# logger.net
KiCad netlist of a schematic drawn in EAGLE
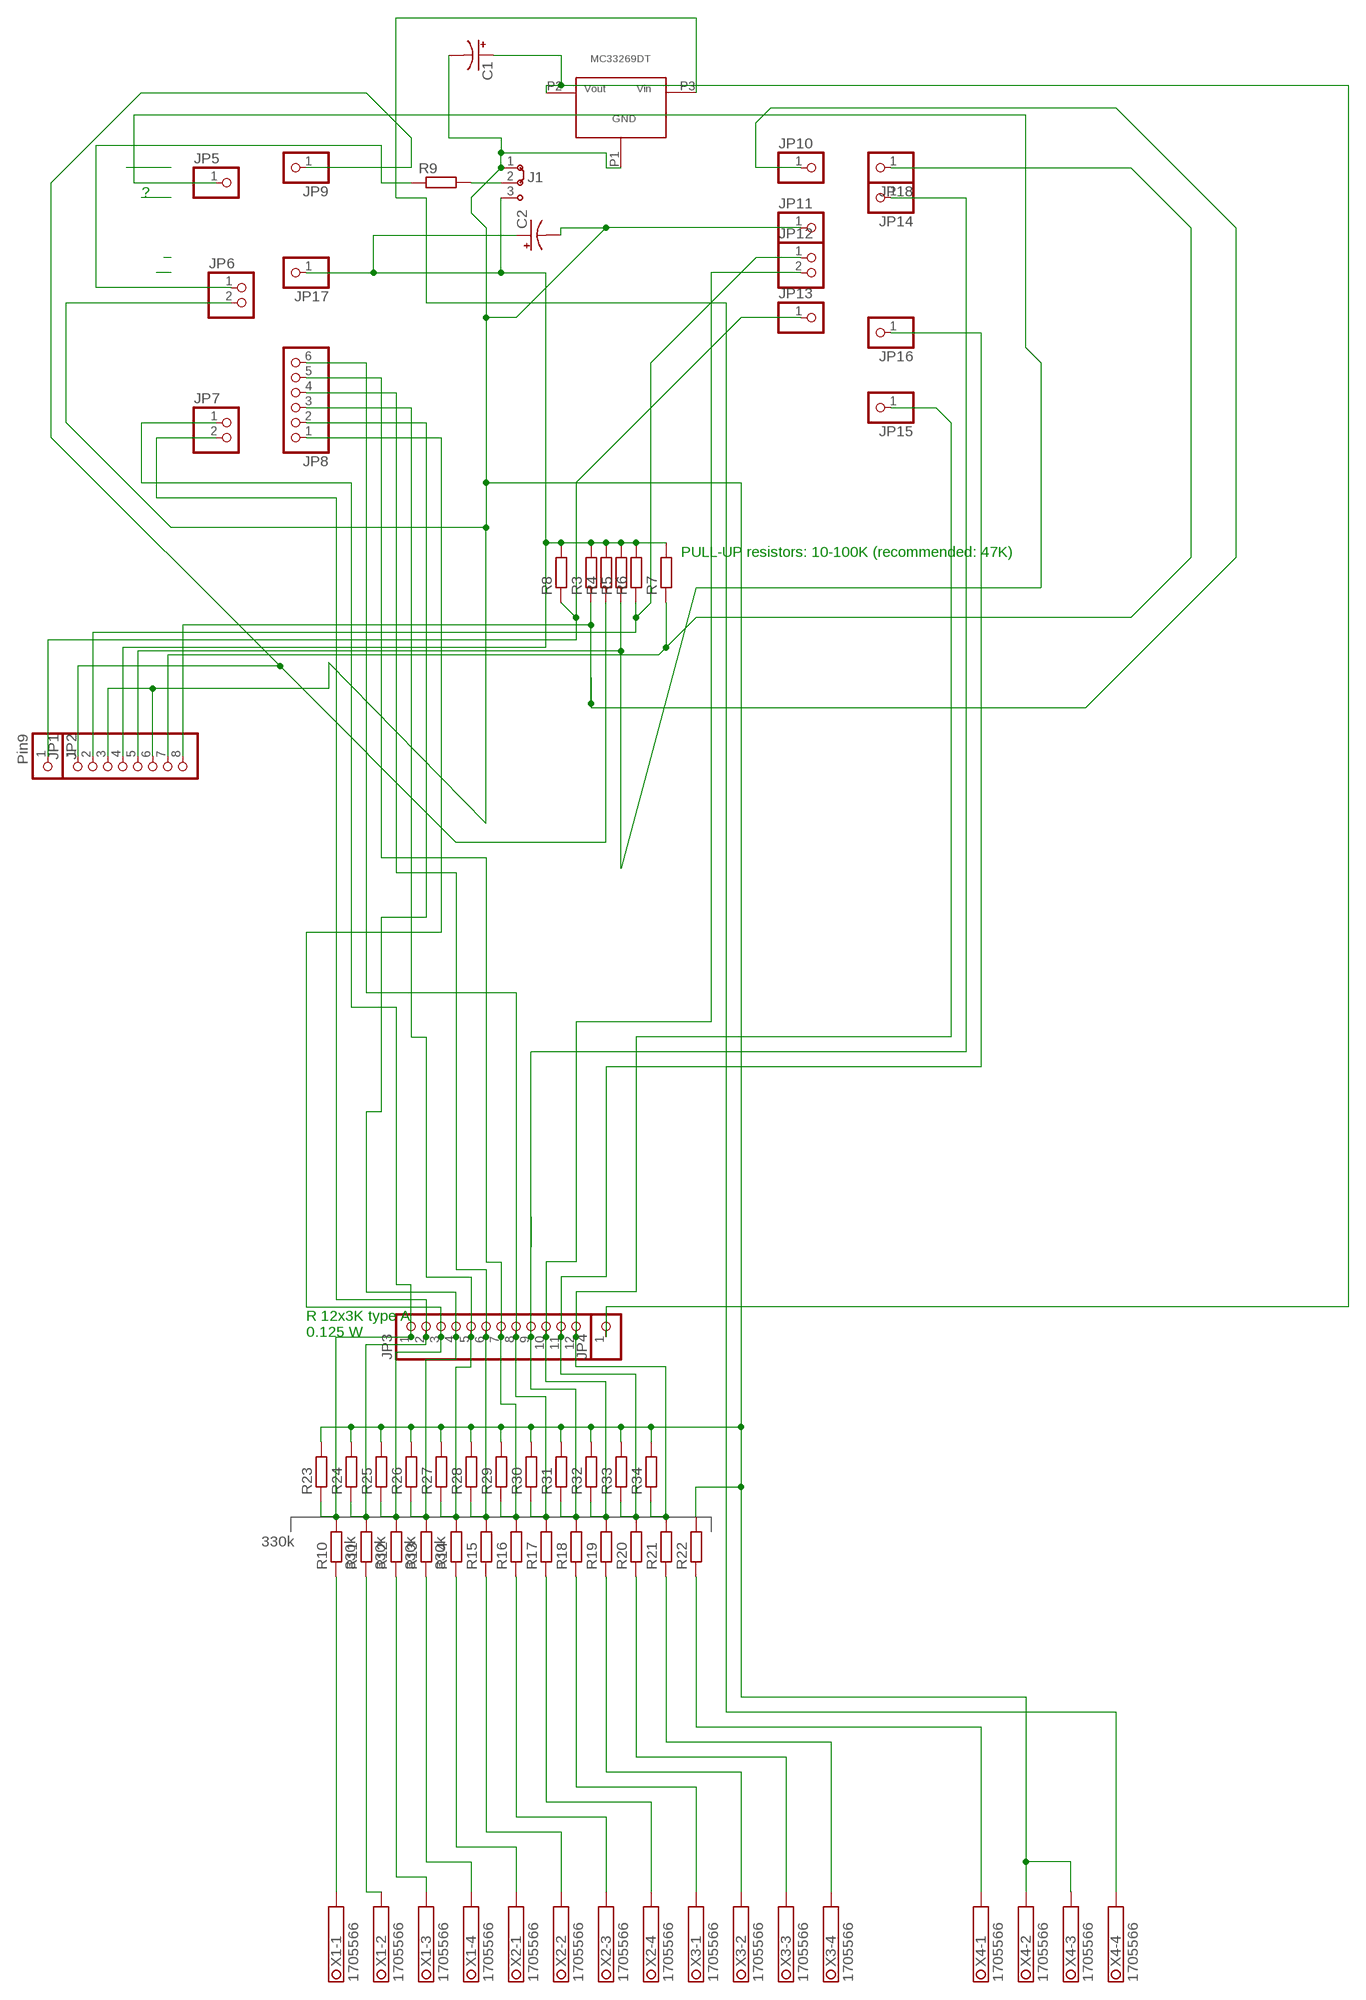
[diagram p0: schematic, sheet 1]

(export (version "E")
  (design (tool "Eeschema 10.0.6"))
  (components
    (comp (ref "C1")
      (value "CPOL-USE5-10.5")
      (footprint "eagle-import:E5-10,5")
      (libsource (lib "eagle-import") (part "CPOL-USE5-10.5"))
    )
    (comp (ref "C2")
      (value "CPOL-USE5-10.5")
      (footprint "eagle-import:E5-10,5")
      (libsource (lib "eagle-import") (part "CPOL-USE5-10.5"))
    )
    (comp (ref "J1")
      (value "J2X2MM")
      (footprint "eagle-import:04C")
      (libsource (lib "eagle-import") (part "J2X2MM"))
    )
    (comp (ref "JP1")
      (value "PINHD-1X8")
      (footprint "eagle-import:1X08")
      (libsource (lib "eagle-import") (part "PINHD-1X8"))
    )
    (comp (ref "JP2")
      (value "Pin9")
      (footprint "eagle-import:1X01")
      (libsource (lib "eagle-import") (part "PINHD-1X1"))
    )
    (comp (ref "JP3")
      (value "PINHD-1X12")
      (footprint "eagle-import:1X12")
      (libsource (lib "eagle-import") (part "PINHD-1X12"))
    )
    (comp (ref "JP4")
      (value "PINHD-1X1")
      (footprint "eagle-import:1X01")
      (libsource (lib "eagle-import") (part "PINHD-1X1"))
    )
    (comp (ref "JP5")
      (value "PINHD-1X1")
      (footprint "eagle-import:1X01")
      (libsource (lib "eagle-import") (part "PINHD-1X1"))
    )
    (comp (ref "JP6")
      (value "PINHD-1X2")
      (footprint "eagle-import:1X02")
      (libsource (lib "eagle-import") (part "PINHD-1X2"))
    )
    (comp (ref "JP7")
      (value "PINHD-1X2")
      (footprint "eagle-import:1X02")
      (libsource (lib "eagle-import") (part "PINHD-1X2"))
    )
    (comp (ref "JP8")
      (value "PINHD-1X6")
      (footprint "eagle-import:1X06")
      (libsource (lib "eagle-import") (part "PINHD-1X6"))
    )
    (comp (ref "JP9")
      (value "PINHD-1X1")
      (footprint "eagle-import:1X01")
      (libsource (lib "eagle-import") (part "PINHD-1X1"))
    )
    (comp (ref "JP10")
      (value "PINHD-1X1")
      (footprint "eagle-import:1X01")
      (libsource (lib "eagle-import") (part "PINHD-1X1"))
    )
    (comp (ref "JP11")
      (value "PINHD-1X1")
      (footprint "eagle-import:1X01")
      (libsource (lib "eagle-import") (part "PINHD-1X1"))
    )
    (comp (ref "JP12")
      (value "PINHD-1X2")
      (footprint "eagle-import:1X02")
      (libsource (lib "eagle-import") (part "PINHD-1X2"))
    )
    (comp (ref "JP13")
      (value "PINHD-1X1")
      (footprint "eagle-import:1X01")
      (libsource (lib "eagle-import") (part "PINHD-1X1"))
    )
    (comp (ref "JP14")
      (value "PINHD-1X1")
      (footprint "eagle-import:1X01")
      (libsource (lib "eagle-import") (part "PINHD-1X1"))
    )
    (comp (ref "JP15")
      (value "PINHD-1X1")
      (footprint "eagle-import:1X01")
      (libsource (lib "eagle-import") (part "PINHD-1X1"))
    )
    (comp (ref "JP16")
      (value "PINHD-1X1")
      (footprint "eagle-import:1X01")
      (libsource (lib "eagle-import") (part "PINHD-1X1"))
    )
    (comp (ref "JP17")
      (value "PINHD-1X1")
      (footprint "eagle-import:1X01")
      (libsource (lib "eagle-import") (part "PINHD-1X1"))
    )
    (comp (ref "JP18")
      (value "PINHD-1X1")
      (footprint "eagle-import:1X01")
      (libsource (lib "eagle-import") (part "PINHD-1X1"))
    )
    (comp (ref "R3")
      (value "R-EU_R1206")
      (footprint "eagle-import:R1206")
      (libsource (lib "eagle-import") (part "R-EU_R1206"))
    )
    (comp (ref "R4")
      (value "R-EU_R1206")
      (footprint "eagle-import:R1206")
      (libsource (lib "eagle-import") (part "R-EU_R1206"))
    )
    (comp (ref "R5")
      (value "R-EU_R1206")
      (footprint "eagle-import:R1206")
      (libsource (lib "eagle-import") (part "R-EU_R1206"))
    )
    (comp (ref "R6")
      (value "R-EU_R1206")
      (footprint "eagle-import:R1206")
      (libsource (lib "eagle-import") (part "R-EU_R1206"))
    )
    (comp (ref "R7")
      (value "R-EU_R1206")
      (footprint "eagle-import:R1206")
      (libsource (lib "eagle-import") (part "R-EU_R1206"))
    )
    (comp (ref "R8")
      (value "R-EU_R1206")
      (footprint "eagle-import:R1206")
      (libsource (lib "eagle-import") (part "R-EU_R1206"))
    )
    (comp (ref "R9")
      (value "R-EU_R1206")
      (footprint "eagle-import:R1206")
      (libsource (lib "eagle-import") (part "R-EU_R1206"))
    )
    (comp (ref "R10")
      (value "330k")
      (footprint "eagle-import:0207_15")
      (libsource (lib "eagle-import") (part "R-EU_0207/15"))
    )
    (comp (ref "R11")
      (value "330k")
      (footprint "eagle-import:0207_15")
      (libsource (lib "eagle-import") (part "R-EU_0207/15"))
    )
    (comp (ref "R12")
      (value "330k")
      (footprint "eagle-import:0207_15")
      (libsource (lib "eagle-import") (part "R-EU_0207/15"))
    )
    (comp (ref "R13")
      (value "330k")
      (footprint "eagle-import:0207_15")
      (libsource (lib "eagle-import") (part "R-EU_0207/15"))
    )
    (comp (ref "R14")
      (value "R-EU_0207/15")
      (footprint "eagle-import:0207_15")
      (libsource (lib "eagle-import") (part "R-EU_0207/15"))
    )
    (comp (ref "R15")
      (value "R-EU_0207/15")
      (footprint "eagle-import:0207_15")
      (libsource (lib "eagle-import") (part "R-EU_0207/15"))
    )
    (comp (ref "R16")
      (value "R-EU_0207/15")
      (footprint "eagle-import:0207_15")
      (libsource (lib "eagle-import") (part "R-EU_0207/15"))
    )
    (comp (ref "R17")
      (value "R-EU_0207/15")
      (footprint "eagle-import:0207_15")
      (libsource (lib "eagle-import") (part "R-EU_0207/15"))
    )
    (comp (ref "R18")
      (value "R-EU_0207/15")
      (footprint "eagle-import:0207_15")
      (libsource (lib "eagle-import") (part "R-EU_0207/15"))
    )
    (comp (ref "R19")
      (value "R-EU_0207/15")
      (footprint "eagle-import:0207_15")
      (libsource (lib "eagle-import") (part "R-EU_0207/15"))
    )
    (comp (ref "R20")
      (value "R-EU_0207/15")
      (footprint "eagle-import:0207_15")
      (libsource (lib "eagle-import") (part "R-EU_0207/15"))
    )
    (comp (ref "R21")
      (value "R-EU_0207/15")
      (footprint "eagle-import:0207_15")
      (libsource (lib "eagle-import") (part "R-EU_0207/15"))
    )
    (comp (ref "R22")
      (value "R-EU_0207/15")
      (footprint "eagle-import:0207_15")
      (libsource (lib "eagle-import") (part "R-EU_0207/15"))
    )
    (comp (ref "R23")
      (value "R-EU_R1206")
      (footprint "eagle-import:R1206")
      (libsource (lib "eagle-import") (part "R-EU_R1206"))
    )
    (comp (ref "R24")
      (value "R-EU_R1206")
      (footprint "eagle-import:R1206")
      (libsource (lib "eagle-import") (part "R-EU_R1206"))
    )
    (comp (ref "R25")
      (value "R-EU_R1206")
      (footprint "eagle-import:R1206")
      (libsource (lib "eagle-import") (part "R-EU_R1206"))
    )
    (comp (ref "R26")
      (value "R-EU_R1206")
      (footprint "eagle-import:R1206")
      (libsource (lib "eagle-import") (part "R-EU_R1206"))
    )
    (comp (ref "R27")
      (value "R-EU_R1206")
      (footprint "eagle-import:R1206")
      (libsource (lib "eagle-import") (part "R-EU_R1206"))
    )
    (comp (ref "R28")
      (value "R-EU_R1206")
      (footprint "eagle-import:R1206")
      (libsource (lib "eagle-import") (part "R-EU_R1206"))
    )
    (comp (ref "R29")
      (value "R-EU_R1206")
      (footprint "eagle-import:R1206")
      (libsource (lib "eagle-import") (part "R-EU_R1206"))
    )
    (comp (ref "R30")
      (value "R-EU_R1206")
      (footprint "eagle-import:R1206")
      (libsource (lib "eagle-import") (part "R-EU_R1206"))
    )
    (comp (ref "R31")
      (value "R-EU_R1206")
      (footprint "eagle-import:R1206")
      (libsource (lib "eagle-import") (part "R-EU_R1206"))
    )
    (comp (ref "R32")
      (value "R-EU_R1206")
      (footprint "eagle-import:R1206")
      (libsource (lib "eagle-import") (part "R-EU_R1206"))
    )
    (comp (ref "R33")
      (value "R-EU_R1206")
      (footprint "eagle-import:R1206")
      (libsource (lib "eagle-import") (part "R-EU_R1206"))
    )
    (comp (ref "R34")
      (value "R-EU_R1206")
      (footprint "eagle-import:R1206")
      (libsource (lib "eagle-import") (part "R-EU_R1206"))
    )
    (comp (ref "U$2")
      (value "MC33269DT")
      (footprint "eagle-import:MC33269DT")
      (libsource (lib "eagle-import") (part "MC33269DT"))
    )
    (comp (ref "X1")
      (value "1705566")
      (footprint "eagle-import:1705566")
      (libsource (lib "eagle-import") (part "1705566"))
    )
    (comp (ref "X2")
      (value "1705566")
      (footprint "eagle-import:1705566")
      (libsource (lib "eagle-import") (part "1705566"))
    )
    (comp (ref "X3")
      (value "1705566")
      (footprint "eagle-import:1705566")
      (libsource (lib "eagle-import") (part "1705566"))
    )
    (comp (ref "X4")
      (value "1705566")
      (footprint "eagle-import:1705566")
      (libsource (lib "eagle-import") (part "1705566"))
    )
  )
  (nets
    (net (code "1") (name "Net-(C2-Pad+)") (class "Default")
      (node (ref "C2") (pin "+") (pinfunction "+_+") (pintype "passive"))
      (node (ref "J1") (pin "3") (pinfunction "3_3") (pintype "passive"))
      (node (ref "JP1") (pin "4") (pinfunction "4_4") (pintype "passive"))
      (node (ref "JP17") (pin "1") (pinfunction "1_1") (pintype "passive"))
      (node (ref "R3") (pin "2") (pinfunction "2_2") (pintype "passive"))
      (node (ref "R4") (pin "2") (pinfunction "2_2") (pintype "passive"))
      (node (ref "R5") (pin "2") (pinfunction "2_2") (pintype "passive"))
      (node (ref "R6") (pin "2") (pinfunction "2_2") (pintype "passive"))
      (node (ref "R7") (pin "2") (pinfunction "2_2") (pintype "passive"))
      (node (ref "R8") (pin "2") (pinfunction "2_2") (pintype "passive"))
    )
    (net (code "2") (name "Net-(J1-Pad2)") (class "Default")
      (node (ref "J1") (pin "2") (pinfunction "2_2") (pintype "passive"))
      (node (ref "R9") (pin "2") (pinfunction "2_2") (pintype "passive"))
    )
    (net (code "3") (name "Net-(JP1-Pad1)") (class "Default")
      (node (ref "JP1") (pin "1") (pinfunction "1_1") (pintype "passive"))
      (node (ref "JP9") (pin "1") (pinfunction "1_1") (pintype "passive"))
      (node (ref "R4") (pin "1") (pinfunction "1_1") (pintype "passive"))
    )
    (net (code "4") (name "Net-(JP1-Pad2)") (class "Default")
      (node (ref "JP1") (pin "2") (pinfunction "2_2") (pintype "passive"))
      (node (ref "JP12") (pin "1") (pinfunction "1_1") (pintype "passive"))
      (node (ref "R6") (pin "1") (pinfunction "1_1") (pintype "passive"))
    )
    (net (code "5") (name "Net-(JP1-Pad5)") (class "Default")
      (node (ref "JP1") (pin "5") (pinfunction "5_5") (pintype "passive"))
      (node (ref "JP5") (pin "1") (pinfunction "1_1") (pintype "passive"))
      (node (ref "R5") (pin "1") (pinfunction "1_1") (pintype "passive"))
    )
    (net (code "6") (name "Net-(JP1-Pad7)") (class "Default")
      (node (ref "JP1") (pin "7") (pinfunction "7_7") (pintype "passive"))
      (node (ref "JP18") (pin "1") (pinfunction "1_1") (pintype "passive"))
      (node (ref "R7") (pin "1") (pinfunction "1_1") (pintype "passive"))
    )
    (net (code "7") (name "Net-(JP1-Pad8)") (class "Default")
      (node (ref "JP1") (pin "8") (pinfunction "8_8") (pintype "passive"))
      (node (ref "JP10") (pin "1") (pinfunction "1_1") (pintype "passive"))
      (node (ref "R3") (pin "1") (pinfunction "1_1") (pintype "passive"))
    )
    (net (code "8") (name "Net-(JP3-Pad1)") (class "Default")
      (node (ref "JP3") (pin "1") (pinfunction "1_1") (pintype "passive"))
      (node (ref "JP7") (pin "1") (pinfunction "1_1") (pintype "passive"))
      (node (ref "R10") (pin "2") (pinfunction "2_2") (pintype "passive"))
      (node (ref "R23") (pin "1") (pinfunction "1_1") (pintype "passive"))
    )
    (net (code "9") (name "Net-(JP3-Pad2)") (class "Default")
      (node (ref "JP3") (pin "2") (pinfunction "2_2") (pintype "passive"))
      (node (ref "JP7") (pin "2") (pinfunction "2_2") (pintype "passive"))
      (node (ref "R11") (pin "2") (pinfunction "2_2") (pintype "passive"))
      (node (ref "R24") (pin "1") (pinfunction "1_1") (pintype "passive"))
    )
    (net (code "10") (name "Net-(JP3-Pad3)") (class "Default")
      (node (ref "JP3") (pin "3") (pinfunction "3_3") (pintype "passive"))
      (node (ref "JP8") (pin "1") (pinfunction "1_1") (pintype "passive"))
      (node (ref "R12") (pin "2") (pinfunction "2_2") (pintype "passive"))
      (node (ref "R25") (pin "1") (pinfunction "1_1") (pintype "passive"))
    )
    (net (code "11") (name "Net-(JP3-Pad4)") (class "Default")
      (node (ref "JP3") (pin "4") (pinfunction "4_4") (pintype "passive"))
      (node (ref "JP8") (pin "2") (pinfunction "2_2") (pintype "passive"))
      (node (ref "R13") (pin "2") (pinfunction "2_2") (pintype "passive"))
      (node (ref "R26") (pin "1") (pinfunction "1_1") (pintype "passive"))
    )
    (net (code "12") (name "Net-(JP3-Pad5)") (class "Default")
      (node (ref "JP3") (pin "5") (pinfunction "5_5") (pintype "passive"))
      (node (ref "JP8") (pin "3") (pinfunction "3_3") (pintype "passive"))
      (node (ref "R14") (pin "2") (pinfunction "2_2") (pintype "passive"))
      (node (ref "R27") (pin "1") (pinfunction "1_1") (pintype "passive"))
    )
    (net (code "13") (name "Net-(JP3-Pad6)") (class "Default")
      (node (ref "JP3") (pin "6") (pinfunction "6_6") (pintype "passive"))
      (node (ref "JP8") (pin "4") (pinfunction "4_4") (pintype "passive"))
      (node (ref "R15") (pin "2") (pinfunction "2_2") (pintype "passive"))
      (node (ref "R28") (pin "1") (pinfunction "1_1") (pintype "passive"))
    )
    (net (code "14") (name "Net-(JP3-Pad7)") (class "Default")
      (node (ref "JP3") (pin "7") (pinfunction "7_7") (pintype "passive"))
      (node (ref "JP8") (pin "5") (pinfunction "5_5") (pintype "passive"))
      (node (ref "R16") (pin "2") (pinfunction "2_2") (pintype "passive"))
      (node (ref "R29") (pin "1") (pinfunction "1_1") (pintype "passive"))
    )
    (net (code "15") (name "Net-(JP3-Pad8)") (class "Default")
      (node (ref "JP3") (pin "8") (pinfunction "8_8") (pintype "passive"))
      (node (ref "JP8") (pin "6") (pinfunction "6_6") (pintype "passive"))
      (node (ref "R17") (pin "2") (pinfunction "2_2") (pintype "passive"))
      (node (ref "R30") (pin "1") (pinfunction "1_1") (pintype "passive"))
    )
    (net (code "16") (name "Net-(JP6-Pad1)") (class "Default")
      (node (ref "JP6") (pin "1") (pinfunction "1_1") (pintype "passive"))
      (node (ref "R9") (pin "1") (pinfunction "1_1") (pintype "passive"))
    )
    (net (code "17") (name "Net-(JP12-Pad2)") (class "Default")
      (node (ref "JP12") (pin "2") (pinfunction "2_2") (pintype "passive"))
      (node (ref "JP3") (pin "10") (pinfunction "10_10") (pintype "passive"))
      (node (ref "R19") (pin "2") (pinfunction "2_2") (pintype "passive"))
      (node (ref "R32") (pin "1") (pinfunction "1_1") (pintype "passive"))
    )
    (net (code "18") (name "Net-(JP13-Pad1)") (class "Default")
      (node (ref "JP13") (pin "1") (pinfunction "1_1") (pintype "passive"))
      (node (ref "JP2") (pin "1") (pinfunction "1_1") (pintype "passive"))
      (node (ref "R8") (pin "1") (pinfunction "1_1") (pintype "passive"))
    )
    (net (code "19") (name "Net-(JP14-Pad1)") (class "Default")
      (node (ref "JP14") (pin "1") (pinfunction "1_1") (pintype "passive"))
      (node (ref "JP3") (pin "9") (pinfunction "9_9") (pintype "passive"))
      (node (ref "R18") (pin "2") (pinfunction "2_2") (pintype "passive"))
      (node (ref "R31") (pin "1") (pinfunction "1_1") (pintype "passive"))
    )
    (net (code "20") (name "Net-(JP15-Pad1)") (class "Default")
      (node (ref "JP15") (pin "1") (pinfunction "1_1") (pintype "passive"))
      (node (ref "JP3") (pin "12") (pinfunction "12_12") (pintype "passive"))
      (node (ref "R21") (pin "2") (pinfunction "2_2") (pintype "passive"))
      (node (ref "R34") (pin "1") (pinfunction "1_1") (pintype "passive"))
    )
    (net (code "21") (name "Net-(JP16-Pad1)") (class "Default")
      (node (ref "JP16") (pin "1") (pinfunction "1_1") (pintype "passive"))
      (node (ref "JP3") (pin "11") (pinfunction "11_11") (pintype "passive"))
      (node (ref "R20") (pin "2") (pinfunction "2_2") (pintype "passive"))
      (node (ref "R33") (pin "1") (pinfunction "1_1") (pintype "passive"))
    )
    (net (code "22") (name "Net-(R10-Pad1)") (class "Default")
      (node (ref "R10") (pin "1") (pinfunction "1_1") (pintype "passive"))
      (node (ref "X1") (pin "1.1") (pinfunction "1A_1.1") (pintype "passive"))
      (node (ref "X1") (pin "1.2") (pinfunction "1A_1.2") (pintype "passive"))
    )
    (net (code "23") (name "Net-(R11-Pad1)") (class "Default")
      (node (ref "R11") (pin "1") (pinfunction "1_1") (pintype "passive"))
      (node (ref "X1") (pin "2.1") (pinfunction "1A_2.1") (pintype "passive"))
      (node (ref "X1") (pin "2.2") (pinfunction "1A_2.2") (pintype "passive"))
    )
    (net (code "24") (name "Net-(R12-Pad1)") (class "Default")
      (node (ref "R12") (pin "1") (pinfunction "1_1") (pintype "passive"))
      (node (ref "X1") (pin "3.1") (pinfunction "1A_3.1") (pintype "passive"))
      (node (ref "X1") (pin "3.2") (pinfunction "1A_3.2") (pintype "passive"))
    )
    (net (code "25") (name "Net-(R13-Pad1)") (class "Default")
      (node (ref "R13") (pin "1") (pinfunction "1_1") (pintype "passive"))
      (node (ref "X1") (pin "4.1") (pinfunction "1A_4.1") (pintype "passive"))
      (node (ref "X1") (pin "4.2") (pinfunction "1A_4.2") (pintype "passive"))
    )
    (net (code "26") (name "Net-(R14-Pad1)") (class "Default")
      (node (ref "R14") (pin "1") (pinfunction "1_1") (pintype "passive"))
      (node (ref "X2") (pin "1.1") (pinfunction "1A_1.1") (pintype "passive"))
      (node (ref "X2") (pin "1.2") (pinfunction "1A_1.2") (pintype "passive"))
    )
    (net (code "27") (name "Net-(R15-Pad1)") (class "Default")
      (node (ref "R15") (pin "1") (pinfunction "1_1") (pintype "passive"))
      (node (ref "X2") (pin "2.1") (pinfunction "1A_2.1") (pintype "passive"))
      (node (ref "X2") (pin "2.2") (pinfunction "1A_2.2") (pintype "passive"))
    )
    (net (code "28") (name "Net-(R16-Pad1)") (class "Default")
      (node (ref "R16") (pin "1") (pinfunction "1_1") (pintype "passive"))
      (node (ref "X2") (pin "3.1") (pinfunction "1A_3.1") (pintype "passive"))
      (node (ref "X2") (pin "3.2") (pinfunction "1A_3.2") (pintype "passive"))
    )
    (net (code "29") (name "Net-(R17-Pad1)") (class "Default")
      (node (ref "R17") (pin "1") (pinfunction "1_1") (pintype "passive"))
      (node (ref "X2") (pin "4.1") (pinfunction "1A_4.1") (pintype "passive"))
      (node (ref "X2") (pin "4.2") (pinfunction "1A_4.2") (pintype "passive"))
    )
    (net (code "30") (name "Net-(R18-Pad1)") (class "Default")
      (node (ref "R18") (pin "1") (pinfunction "1_1") (pintype "passive"))
      (node (ref "X3") (pin "1.1") (pinfunction "1A_1.1") (pintype "passive"))
      (node (ref "X3") (pin "1.2") (pinfunction "1A_1.2") (pintype "passive"))
    )
    (net (code "31") (name "Net-(R19-Pad1)") (class "Default")
      (node (ref "R19") (pin "1") (pinfunction "1_1") (pintype "passive"))
      (node (ref "X3") (pin "2.1") (pinfunction "1A_2.1") (pintype "passive"))
      (node (ref "X3") (pin "2.2") (pinfunction "1A_2.2") (pintype "passive"))
    )
    (net (code "32") (name "Net-(R20-Pad1)") (class "Default")
      (node (ref "R20") (pin "1") (pinfunction "1_1") (pintype "passive"))
      (node (ref "X3") (pin "3.1") (pinfunction "1A_3.1") (pintype "passive"))
      (node (ref "X3") (pin "3.2") (pinfunction "1A_3.2") (pintype "passive"))
    )
    (net (code "33") (name "Net-(R21-Pad1)") (class "Default")
      (node (ref "R21") (pin "1") (pinfunction "1_1") (pintype "passive"))
      (node (ref "X3") (pin "4.1") (pinfunction "1A_4.1") (pintype "passive"))
      (node (ref "X3") (pin "4.2") (pinfunction "1A_4.2") (pintype "passive"))
    )
    (net (code "34") (name "Net-(R22-Pad1)") (class "Default")
      (node (ref "R22") (pin "1") (pinfunction "1_1") (pintype "passive"))
      (node (ref "X4") (pin "1.1") (pinfunction "1A_1.1") (pintype "passive"))
      (node (ref "X4") (pin "1.2") (pinfunction "1A_1.2") (pintype "passive"))
    )
    (net (code "35") (name "Net-(U$2-GND)") (class "Default")
      (node (ref "C1") (pin "-") (pinfunction "-_-") (pintype "passive"))
      (node (ref "C2") (pin "-") (pinfunction "-_-") (pintype "passive"))
      (node (ref "J1") (pin "1") (pinfunction "1_1") (pintype "passive"))
      (node (ref "JP1") (pin "3") (pinfunction "3_3") (pintype "passive"))
      (node (ref "JP1") (pin "6") (pinfunction "6_6") (pintype "passive"))
      (node (ref "JP11") (pin "1") (pinfunction "1_1") (pintype "passive"))
      (node (ref "JP6") (pin "2") (pinfunction "2_2") (pintype "passive"))
      (node (ref "R22") (pin "2") (pinfunction "2_2") (pintype "passive"))
      (node (ref "R23") (pin "2") (pinfunction "2_2") (pintype "passive"))
      (node (ref "R24") (pin "2") (pinfunction "2_2") (pintype "passive"))
      (node (ref "R25") (pin "2") (pinfunction "2_2") (pintype "passive"))
      (node (ref "R26") (pin "2") (pinfunction "2_2") (pintype "passive"))
      (node (ref "R27") (pin "2") (pinfunction "2_2") (pintype "passive"))
      (node (ref "R28") (pin "2") (pinfunction "2_2") (pintype "passive"))
      (node (ref "R29") (pin "2") (pinfunction "2_2") (pintype "passive"))
      (node (ref "R30") (pin "2") (pinfunction "2_2") (pintype "passive"))
      (node (ref "R31") (pin "2") (pinfunction "2_2") (pintype "passive"))
      (node (ref "R32") (pin "2") (pinfunction "2_2") (pintype "passive"))
      (node (ref "R33") (pin "2") (pinfunction "2_2") (pintype "passive"))
      (node (ref "R34") (pin "2") (pinfunction "2_2") (pintype "passive"))
      (node (ref "U$2") (pin "P1") (pinfunction "GND_P1") (pintype "power_in"))
      (node (ref "X4") (pin "2.1") (pinfunction "1A_2.1") (pintype "passive"))
      (node (ref "X4") (pin "2.2") (pinfunction "1A_2.2") (pintype "passive"))
      (node (ref "X4") (pin "3.1") (pinfunction "1A_3.1") (pintype "passive"))
      (node (ref "X4") (pin "3.2") (pinfunction "1A_3.2") (pintype "passive"))
    )
    (net (code "36") (name "Net-(U$2-VIN)") (class "Default")
      (node (ref "U$2") (pin "P3") (pinfunction "VIN_P3") (pintype "input"))
      (node (ref "X4") (pin "4.1") (pinfunction "1A_4.1") (pintype "passive"))
      (node (ref "X4") (pin "4.2") (pinfunction "1A_4.2") (pintype "passive"))
    )
    (net (code "37") (name "Net-(U$2-VOUT)") (class "Default")
      (node (ref "C1") (pin "+") (pinfunction "+_+") (pintype "passive"))
      (node (ref "JP4") (pin "1") (pinfunction "1_1") (pintype "passive"))
      (node (ref "U$2") (pin "P2") (pinfunction "VOUT_P2") (pintype "output"))
    )
  )
)
